# 24V-5V.net
KiCad netlist of a schematic drawn in Altium Designer
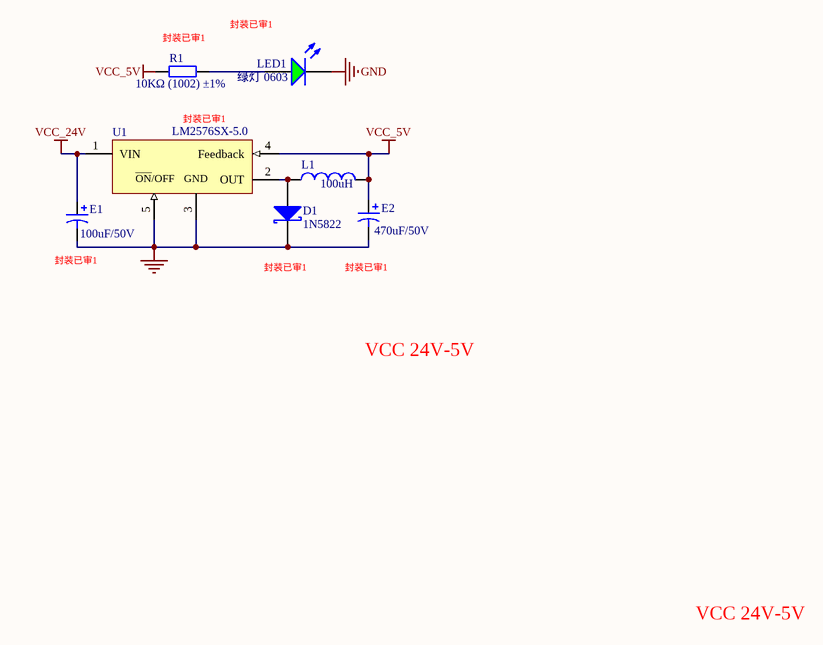
[diagram p0: 24V-5V.SchDoc]

(export (version "E")
  (design (tool "Eeschema 10.0.6"))
  (components
    (comp (ref "D1")
      (value "1N5822")
      (footprint "DO214_SMA")
      (description "整流二极管")
      (libsource (lib "二极管") (part "SMA(DO-214AC) 1N5822"))
    )
    (comp (ref "E1")
      (value "100uF/50V")
      (footprint "CAP_PR_3.5_8")
      (description "Polarized Capacitor (Radial)")
      (fields (field (name "Comment") "Cap Pol1") (field (name "PUBLISHER") "Altium Limited"))
      (libsource (lib "Miscellaneous Devices") (part "Cap Pol1"))
    )
    (comp (ref "E2")
      (value "470uF/50V")
      (footprint "CAP_PR_5.0_13")
      (description "Polarized Capacitor (Radial)")
      (fields (field (name "Comment") "Cap Pol1") (field (name "PUBLISHER") "Altium Limited"))
      (libsource (lib "Miscellaneous Devices") (part "Cap Pol1"))
    )
    (comp (ref "L1")
      (value "100uH")
      (footprint "Inductor_CDRH127R")
      (description "Inductor")
      (fields (field (name "PUBLISHER") "Altium Limited"))
      (libsource (lib "Miscellaneous Devices") (part "Inductor"))
    )
    (comp (ref "LED1")
      (value "绿灯 0603")
      (footprint "LED_0603_G")
      (description "发光二极管")
      (libsource (lib "LED") (part "0603 绿灯"))
    )
    (comp (ref "R1")
      (value "10KΩ (1002) ±1%")
      (footprint "RESC_0603_2")
      (description "贴片电阻")
      (libsource (lib "RES") (part "0603 10KΩ (1002) 1%"))
    )
    (comp (ref "U1")
      (value "LM2576SX-5.0")
      (footprint "TO263_5")
      (description "DC-DC芯片")
      (libsource (lib "IC芯片") (part "LM2576SX-5.0_[C34465]"))
    )
  )
  (nets
    (net (code "1") (name "GND") (class "Default")
      (node (ref "D1") (pin "2") (pinfunction "K_2") (pintype "passive"))
      (node (ref "E1") (pin "2") (pinfunction "2_2") (pintype "passive"))
      (node (ref "E2") (pin "2") (pinfunction "2_2") (pintype "passive"))
      (node (ref "LED1") (pin "K") (pinfunction "K_K") (pintype "passive"))
      (node (ref "U1") (pin "3") (pinfunction "DGND_3") (pintype "passive"))
      (node (ref "U1") (pin "5") (pinfunction "ON/OFF_5") (pintype "input"))
    )
    (net (code "2") (name "Net-(D1-A)") (class "Default")
      (node (ref "D1") (pin "1") (pinfunction "A_1") (pintype "passive"))
      (node (ref "L1") (pin "1") (pinfunction "1_1") (pintype "passive"))
      (node (ref "U1") (pin "2") (pinfunction "OUT_2") (pintype "passive"))
    )
    (net (code "3") (name "Net-(LED1-PadA)") (class "Default")
      (node (ref "LED1") (pin "A") (pinfunction "A_A") (pintype "passive"))
      (node (ref "R1") (pin "2") (pinfunction "2_2") (pintype "passive"))
    )
    (net (code "4") (name "VCC_5V") (class "Default")
      (node (ref "E2") (pin "1") (pinfunction "1_1") (pintype "passive"))
      (node (ref "L1") (pin "2") (pinfunction "2_2") (pintype "passive"))
      (node (ref "U1") (pin "4") (pinfunction "Feedback_4") (pintype "input"))
    )
    (net (code "5") (name "VCC_24V") (class "Default")
      (node (ref "E1") (pin "1") (pinfunction "1_1") (pintype "passive"))
      (node (ref "U1") (pin "1") (pinfunction "VIN_1") (pintype "passive"))
    )
    (net (code "6") (name "unconnected-(R1-Pad1)") (class "Default")
      (node (ref "R1") (pin "1") (pinfunction "1_1") (pintype "passive"))
    )
  )
)
